# v2.net
KiCad netlist of a schematic drawn in EAGLE
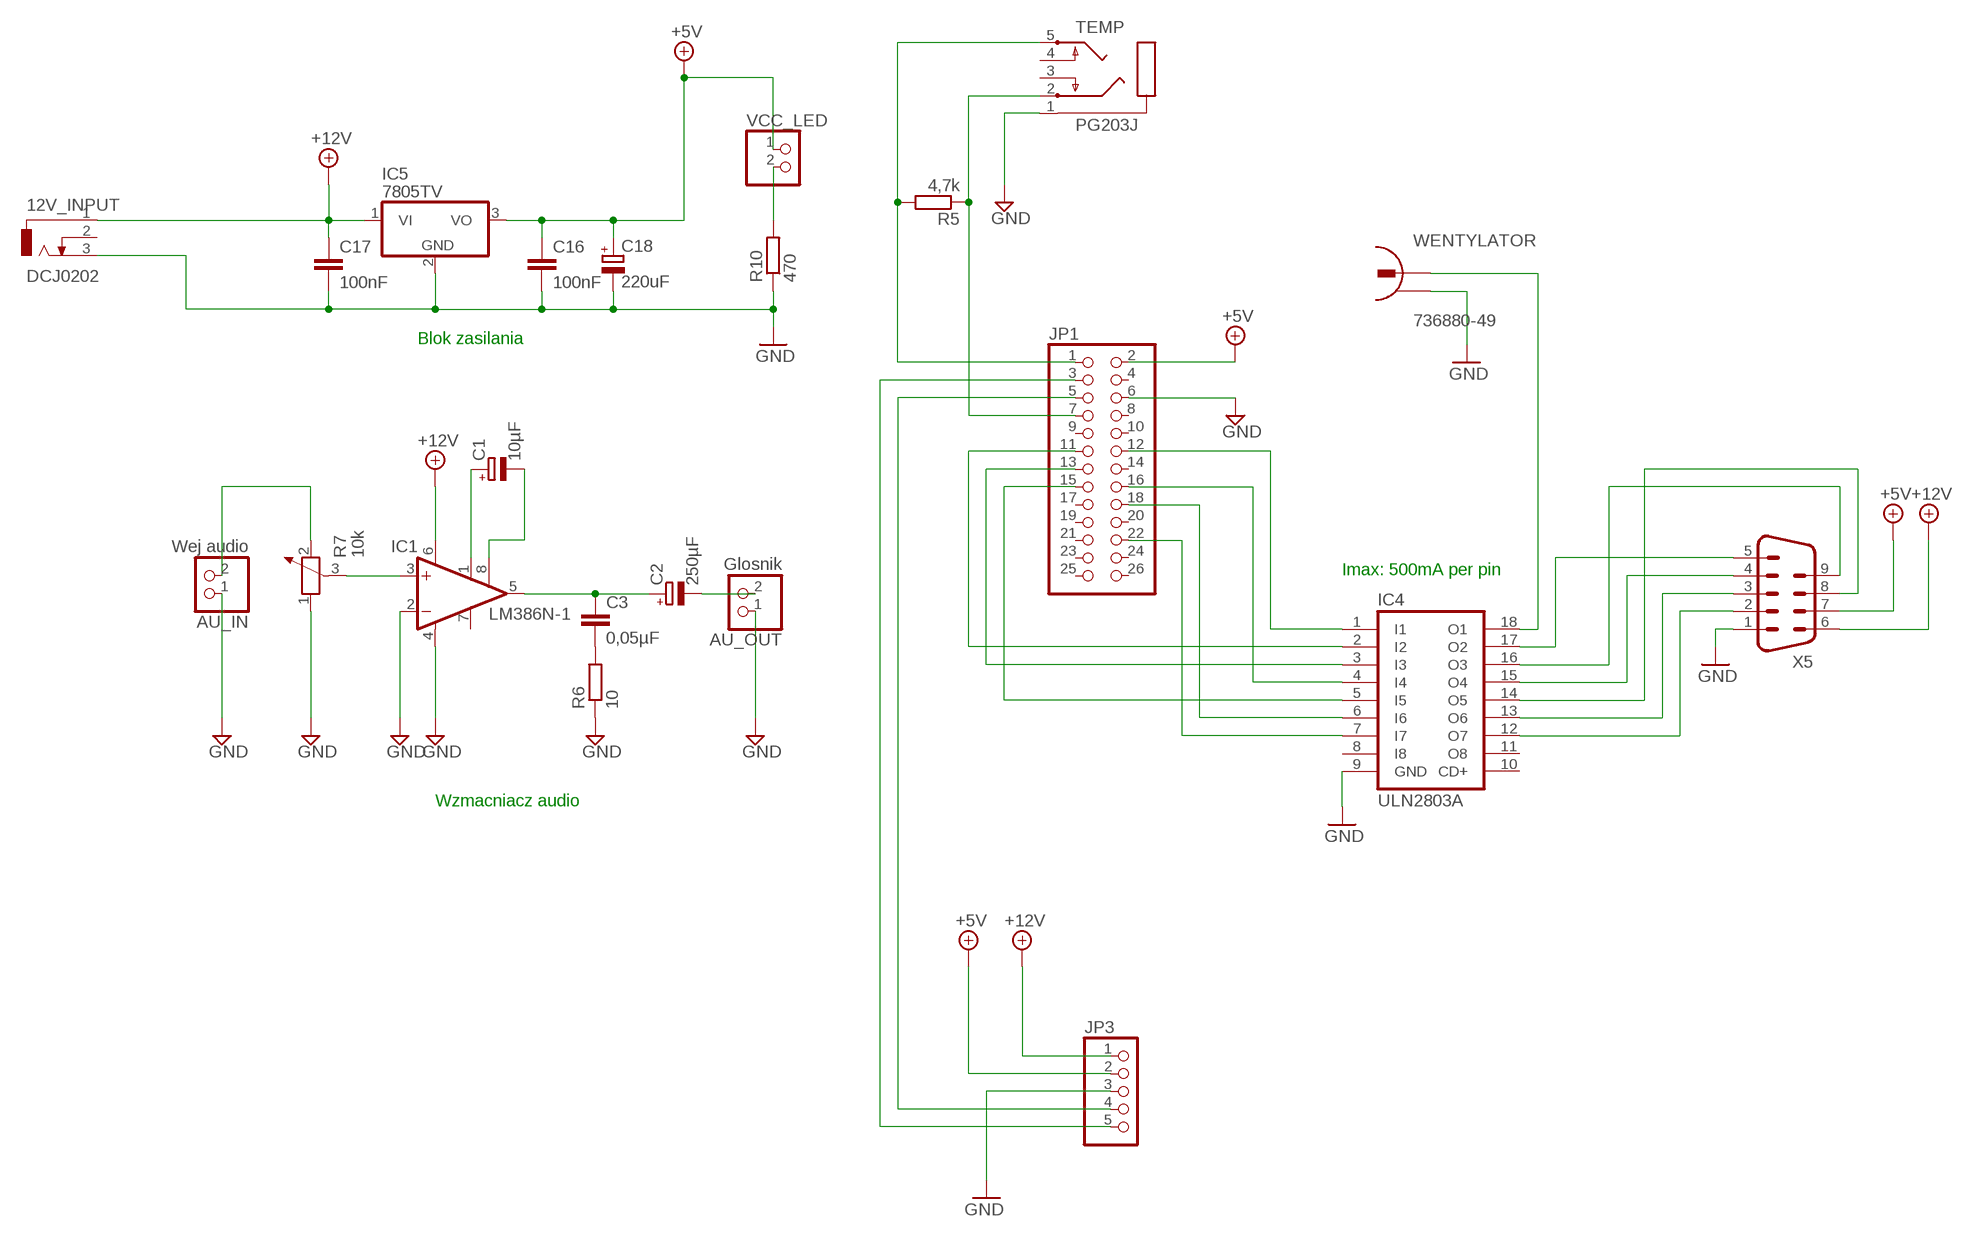
[diagram p0: schematic, sheet 1]

(export (version "E")
  (design (tool "Eeschema 10.0.6"))
  (components
    (comp (ref "12V_INPUT")
      (value "DCJ0202")
      (footprint "eagle-import:DCJ0202")
      (libsource (lib "eagle-import") (part "DCJ0202"))
    )
    (comp (ref "AU_IN")
      (value "Wej audio")
      (footprint "eagle-import:1X02")
      (libsource (lib "eagle-import") (part "PINHD-1X2"))
    )
    (comp (ref "AU_OUT")
      (value "Glosnik")
      (footprint "eagle-import:1X02")
      (libsource (lib "eagle-import") (part "PINHD-1X2"))
    )
    (comp (ref "C1")
      (value "10µF")
      (footprint "eagle-import:E2,5-5")
      (libsource (lib "eagle-import") (part "rcl_CPOL-EUE2.5-5"))
    )
    (comp (ref "C2")
      (value "250µF")
      (footprint "eagle-import:E2,5-6")
      (libsource (lib "eagle-import") (part "rcl_CPOL-EUE2.5-6"))
    )
    (comp (ref "C3")
      (value "0,05µF")
      (footprint "eagle-import:C025-024X044")
      (libsource (lib "eagle-import") (part "rcl_C-EU025-024X044"))
    )
    (comp (ref "C16")
      (value "100nF")
      (footprint "eagle-import:C050-024X044")
      (libsource (lib "eagle-import") (part "C-EU050-024X044"))
    )
    (comp (ref "C17")
      (value "100nF")
      (footprint "eagle-import:C050-024X044")
      (libsource (lib "eagle-import") (part "C-EU050-024X044"))
    )
    (comp (ref "C18")
      (value "220uF")
      (footprint "eagle-import:E2,5-5")
      (libsource (lib "eagle-import") (part "CPOL-EUE2.5-5"))
    )
    (comp (ref "IC1")
      (value "LM386N-1")
      (footprint "eagle-import:DIL08")
      (libsource (lib "eagle-import") (part "LM386?-N1"))
    )
    (comp (ref "IC4")
      (value "ULN2803A")
      (footprint "eagle-import:DIL18")
      (libsource (lib "eagle-import") (part "ULN2803A"))
    )
    (comp (ref "IC5")
      (value "7805TV")
      (footprint "eagle-import:TO220V")
      (libsource (lib "eagle-import") (part "78TV05"))
    )
    (comp (ref "JP1")
      (value "PINHD-2X13")
      (footprint "eagle-import:2X13")
      (libsource (lib "eagle-import") (part "PINHD-2X13"))
    )
    (comp (ref "JP3")
      (value "PINHD-1X5/90")
      (footprint "eagle-import:1X05_90")
      (libsource (lib "eagle-import") (part "PINHD-1X5/90"))
    )
    (comp (ref "R5")
      (value "4,7k")
      (footprint "eagle-import:R1206")
      (libsource (lib "eagle-import") (part "R-EU_R1206"))
    )
    (comp (ref "R6")
      (value "10")
      (footprint "eagle-import:R1206")
      (libsource (lib "eagle-import") (part "R-EU_R1206"))
    )
    (comp (ref "R7")
      (value "10k")
      (footprint "eagle-import:PT-10")
      (libsource (lib "eagle-import") (part "POTENTIOMETER_PT-10"))
    )
    (comp (ref "R10")
      (value "470")
      (footprint "eagle-import:R1206")
      (libsource (lib "eagle-import") (part "R-EU_R1206"))
    )
    (comp (ref "TEMP")
      (value "PG203J")
      (footprint "eagle-import:PG203J")
      (libsource (lib "eagle-import") (part "PG203J"))
    )
    (comp (ref "VCC_LED")
      (value "PINHD-1X2")
      (footprint "eagle-import:1X02")
      (libsource (lib "eagle-import") (part "PINHD-1X2"))
    )
    (comp (ref "WENTYLATOR")
      (value "736880-49")
      (footprint "eagle-import:736880-49")
      (libsource (lib "eagle-import") (part "736880-49"))
    )
    (comp (ref "X5")
      (value "M09H")
      (footprint "eagle-import:M09H")
      (libsource (lib "eagle-import") (part "M09H"))
    )
  )
  (nets
    (net (code "1") (name "+5V") (class "Default")
      (node (ref "C16") (pin "1") (pinfunction "1_1") (pintype "passive"))
      (node (ref "C18") (pin "+") (pinfunction "+_+") (pintype "passive"))
      (node (ref "IC5") (pin "3") (pinfunction "VO_3") (pintype "passive"))
      (node (ref "JP1") (pin "2") (pinfunction "2_2") (pintype "passive"))
      (node (ref "JP3") (pin "2") (pinfunction "2_2") (pintype "passive"))
      (node (ref "VCC_LED") (pin "1") (pinfunction "1_1") (pintype "passive"))
      (node (ref "X5") (pin "7") (pinfunction "7_7") (pintype "passive"))
    )
    (net (code "2") (name "+12V") (class "Default")
      (node (ref "12V_INPUT") (pin "1") (pinfunction "1_1") (pintype "passive"))
      (node (ref "C17") (pin "1") (pinfunction "1_1") (pintype "passive"))
      (node (ref "IC1") (pin "6") (pinfunction "VS_6") (pintype "power_in"))
      (node (ref "IC5") (pin "1") (pinfunction "VI_1") (pintype "input"))
      (node (ref "JP3") (pin "1") (pinfunction "1_1") (pintype "passive"))
      (node (ref "X5") (pin "6") (pinfunction "6_6") (pintype "passive"))
    )
    (net (code "3") (name "GND") (class "Default")
      (node (ref "12V_INPUT") (pin "3") (pinfunction "3_3") (pintype "passive"))
      (node (ref "AU_IN") (pin "1") (pinfunction "1_1") (pintype "passive"))
      (node (ref "AU_OUT") (pin "1") (pinfunction "1_1") (pintype "passive"))
      (node (ref "C16") (pin "2") (pinfunction "2_2") (pintype "passive"))
      (node (ref "C17") (pin "2") (pinfunction "2_2") (pintype "passive"))
      (node (ref "C18") (pin "-") (pinfunction "-_-") (pintype "passive"))
      (node (ref "IC1") (pin "2") (pinfunction "-IN_2") (pintype "input"))
      (node (ref "IC1") (pin "4") (pinfunction "GND_4") (pintype "power_in"))
      (node (ref "IC4") (pin "9") (pinfunction "GND_9") (pintype "power_in"))
      (node (ref "IC5") (pin "2") (pinfunction "GND_2") (pintype "passive"))
      (node (ref "JP1") (pin "6") (pinfunction "6_6") (pintype "passive"))
      (node (ref "JP3") (pin "3") (pinfunction "3_3") (pintype "passive"))
      (node (ref "R10") (pin "1") (pinfunction "1_1") (pintype "passive"))
      (node (ref "R6") (pin "1") (pinfunction "1_1") (pintype "passive"))
      (node (ref "R7") (pin "1") (pinfunction "1_1") (pintype "passive"))
      (node (ref "TEMP") (pin "1") (pinfunction "1_1") (pintype "passive"))
      (node (ref "WENTYLATOR") (pin "2") (pinfunction "2_2") (pintype "passive"))
      (node (ref "X5") (pin "1") (pinfunction "1_1") (pintype "passive"))
    )
    (net (code "4") (name "Net-(AU_IN-Pad2)") (class "Default")
      (node (ref "AU_IN") (pin "2") (pinfunction "2_2") (pintype "passive"))
      (node (ref "R7") (pin "2") (pinfunction "2_2") (pintype "passive"))
    )
    (net (code "5") (name "Net-(AU_OUT-Pad2)") (class "Default")
      (node (ref "AU_OUT") (pin "2") (pinfunction "2_2") (pintype "passive"))
      (node (ref "C2") (pin "-") (pinfunction "-_-") (pintype "passive"))
    )
    (net (code "6") (name "Net-(C1-Pad+)") (class "Default")
      (node (ref "C1") (pin "+") (pinfunction "+_+") (pintype "passive"))
      (node (ref "IC1") (pin "1") (pinfunction "GAIN_1") (pintype "passive"))
    )
    (net (code "7") (name "Net-(C1-Pad-)") (class "Default")
      (node (ref "C1") (pin "-") (pinfunction "-_-") (pintype "passive"))
      (node (ref "IC1") (pin "8") (pinfunction "GAIN_8") (pintype "passive"))
    )
    (net (code "8") (name "Net-(C3-Pad2)") (class "Default")
      (node (ref "C3") (pin "2") (pinfunction "2_2") (pintype "passive"))
      (node (ref "R6") (pin "2") (pinfunction "2_2") (pintype "passive"))
    )
    (net (code "9") (name "Net-(IC1-+IN)") (class "Default")
      (node (ref "IC1") (pin "3") (pinfunction "+IN_3") (pintype "input"))
      (node (ref "R7") (pin "3") (pinfunction "3_3") (pintype "passive"))
    )
    (net (code "10") (name "Net-(IC1-OUT)") (class "Default")
      (node (ref "C2") (pin "+") (pinfunction "+_+") (pintype "passive"))
      (node (ref "C3") (pin "1") (pinfunction "1_1") (pintype "passive"))
      (node (ref "IC1") (pin "5") (pinfunction "OUT_5") (pintype "output"))
    )
    (net (code "11") (name "Net-(IC4-I1)") (class "Default")
      (node (ref "IC4") (pin "1") (pinfunction "I1_1") (pintype "input"))
      (node (ref "JP1") (pin "12") (pinfunction "12_12") (pintype "passive"))
    )
    (net (code "12") (name "Net-(IC4-I2)") (class "Default")
      (node (ref "IC4") (pin "2") (pinfunction "I2_2") (pintype "input"))
      (node (ref "JP1") (pin "11") (pinfunction "11_11") (pintype "passive"))
    )
    (net (code "13") (name "Net-(IC4-I3)") (class "Default")
      (node (ref "IC4") (pin "3") (pinfunction "I3_3") (pintype "input"))
      (node (ref "JP1") (pin "13") (pinfunction "13_13") (pintype "passive"))
    )
    (net (code "14") (name "Net-(IC4-I4)") (class "Default")
      (node (ref "IC4") (pin "4") (pinfunction "I4_4") (pintype "input"))
      (node (ref "JP1") (pin "16") (pinfunction "16_16") (pintype "passive"))
    )
    (net (code "15") (name "Net-(IC4-I5)") (class "Default")
      (node (ref "IC4") (pin "5") (pinfunction "I5_5") (pintype "input"))
      (node (ref "JP1") (pin "15") (pinfunction "15_15") (pintype "passive"))
    )
    (net (code "16") (name "Net-(IC4-I6)") (class "Default")
      (node (ref "IC4") (pin "6") (pinfunction "I6_6") (pintype "input"))
      (node (ref "JP1") (pin "18") (pinfunction "18_18") (pintype "passive"))
    )
    (net (code "17") (name "Net-(IC4-I7)") (class "Default")
      (node (ref "IC4") (pin "7") (pinfunction "I7_7") (pintype "input"))
      (node (ref "JP1") (pin "22") (pinfunction "22_22") (pintype "passive"))
    )
    (net (code "18") (name "Net-(IC4-O1)") (class "Default")
      (node (ref "IC4") (pin "18") (pinfunction "O1_18") (pintype "open_collector"))
      (node (ref "WENTYLATOR") (pin "1") (pinfunction "1_1") (pintype "passive"))
    )
    (net (code "19") (name "Net-(IC4-O2)") (class "Default")
      (node (ref "IC4") (pin "17") (pinfunction "O2_17") (pintype "open_collector"))
      (node (ref "X5") (pin "5") (pinfunction "5_5") (pintype "passive"))
    )
    (net (code "20") (name "Net-(IC4-O3)") (class "Default")
      (node (ref "IC4") (pin "16") (pinfunction "O3_16") (pintype "open_collector"))
      (node (ref "X5") (pin "9") (pinfunction "9_9") (pintype "passive"))
    )
    (net (code "21") (name "Net-(IC4-O4)") (class "Default")
      (node (ref "IC4") (pin "15") (pinfunction "O4_15") (pintype "open_collector"))
      (node (ref "X5") (pin "4") (pinfunction "4_4") (pintype "passive"))
    )
    (net (code "22") (name "Net-(IC4-O5)") (class "Default")
      (node (ref "IC4") (pin "14") (pinfunction "O5_14") (pintype "open_collector"))
      (node (ref "X5") (pin "8") (pinfunction "8_8") (pintype "passive"))
    )
    (net (code "23") (name "Net-(IC4-O6)") (class "Default")
      (node (ref "IC4") (pin "13") (pinfunction "O6_13") (pintype "open_collector"))
      (node (ref "X5") (pin "3") (pinfunction "3_3") (pintype "passive"))
    )
    (net (code "24") (name "Net-(IC4-O7)") (class "Default")
      (node (ref "IC4") (pin "12") (pinfunction "O7_12") (pintype "open_collector"))
      (node (ref "X5") (pin "2") (pinfunction "2_2") (pintype "passive"))
    )
    (net (code "25") (name "Net-(JP1-Pad1)") (class "Default")
      (node (ref "JP1") (pin "1") (pinfunction "1_1") (pintype "passive"))
      (node (ref "R5") (pin "2") (pinfunction "2_2") (pintype "passive"))
      (node (ref "TEMP") (pin "5") (pinfunction "5_5") (pintype "passive"))
    )
    (net (code "26") (name "Net-(JP1-Pad3)") (class "Default")
      (node (ref "JP1") (pin "3") (pinfunction "3_3") (pintype "passive"))
      (node (ref "JP3") (pin "5") (pinfunction "5_5") (pintype "passive"))
    )
    (net (code "27") (name "Net-(JP1-Pad5)") (class "Default")
      (node (ref "JP1") (pin "5") (pinfunction "5_5") (pintype "passive"))
      (node (ref "JP3") (pin "4") (pinfunction "4_4") (pintype "passive"))
    )
    (net (code "28") (name "Net-(JP1-Pad7)") (class "Default")
      (node (ref "JP1") (pin "7") (pinfunction "7_7") (pintype "passive"))
      (node (ref "R5") (pin "1") (pinfunction "1_1") (pintype "passive"))
      (node (ref "TEMP") (pin "2") (pinfunction "2_2") (pintype "passive"))
    )
    (net (code "29") (name "Net-(R10-Pad2)") (class "Default")
      (node (ref "R10") (pin "2") (pinfunction "2_2") (pintype "passive"))
      (node (ref "VCC_LED") (pin "2") (pinfunction "2_2") (pintype "passive"))
    )
    (net (code "30") (name "unconnected-(12V_INPUT-Pad2)") (class "Default")
      (node (ref "12V_INPUT") (pin "2") (pinfunction "2_2") (pintype "passive"))
    )
    (net (code "31") (name "unconnected-(IC1-BYPASS-Pad7)") (class "Default")
      (node (ref "IC1") (pin "7") (pinfunction "BYPASS_7") (pintype "passive"))
    )
    (net (code "32") (name "unconnected-(IC4-CD+-Pad10)") (class "Default")
      (node (ref "IC4") (pin "10") (pinfunction "CD+_10") (pintype "passive"))
    )
    (net (code "33") (name "unconnected-(IC4-I8-Pad8)") (class "Default")
      (node (ref "IC4") (pin "8") (pinfunction "I8_8") (pintype "input"))
    )
    (net (code "34") (name "unconnected-(IC4-O8-Pad11)") (class "Default")
      (node (ref "IC4") (pin "11") (pinfunction "O8_11") (pintype "open_collector"))
    )
    (net (code "35") (name "unconnected-(JP1-Pad4)") (class "Default")
      (node (ref "JP1") (pin "4") (pinfunction "4_4") (pintype "passive"))
    )
    (net (code "36") (name "unconnected-(JP1-Pad8)") (class "Default")
      (node (ref "JP1") (pin "8") (pinfunction "8_8") (pintype "passive"))
    )
    (net (code "37") (name "unconnected-(JP1-Pad9)") (class "Default")
      (node (ref "JP1") (pin "9") (pinfunction "9_9") (pintype "passive"))
    )
    (net (code "38") (name "unconnected-(JP1-Pad10)") (class "Default")
      (node (ref "JP1") (pin "10") (pinfunction "10_10") (pintype "passive"))
    )
    (net (code "39") (name "unconnected-(JP1-Pad14)") (class "Default")
      (node (ref "JP1") (pin "14") (pinfunction "14_14") (pintype "passive"))
    )
    (net (code "40") (name "unconnected-(JP1-Pad17)") (class "Default")
      (node (ref "JP1") (pin "17") (pinfunction "17_17") (pintype "passive"))
    )
    (net (code "41") (name "unconnected-(JP1-Pad19)") (class "Default")
      (node (ref "JP1") (pin "19") (pinfunction "19_19") (pintype "passive"))
    )
    (net (code "42") (name "unconnected-(JP1-Pad20)") (class "Default")
      (node (ref "JP1") (pin "20") (pinfunction "20_20") (pintype "passive"))
    )
    (net (code "43") (name "unconnected-(JP1-Pad21)") (class "Default")
      (node (ref "JP1") (pin "21") (pinfunction "21_21") (pintype "passive"))
    )
    (net (code "44") (name "unconnected-(JP1-Pad23)") (class "Default")
      (node (ref "JP1") (pin "23") (pinfunction "23_23") (pintype "passive"))
    )
    (net (code "45") (name "unconnected-(JP1-Pad24)") (class "Default")
      (node (ref "JP1") (pin "24") (pinfunction "24_24") (pintype "passive"))
    )
    (net (code "46") (name "unconnected-(JP1-Pad25)") (class "Default")
      (node (ref "JP1") (pin "25") (pinfunction "25_25") (pintype "passive"))
    )
    (net (code "47") (name "unconnected-(JP1-Pad26)") (class "Default")
      (node (ref "JP1") (pin "26") (pinfunction "26_26") (pintype "passive"))
    )
    (net (code "48") (name "unconnected-(TEMP-Pad3)") (class "Default")
      (node (ref "TEMP") (pin "3") (pinfunction "3_3") (pintype "passive"))
    )
    (net (code "49") (name "unconnected-(TEMP-Pad4)") (class "Default")
      (node (ref "TEMP") (pin "4") (pinfunction "4_4") (pintype "passive"))
    )
    (net (code "50") (name "unconnected-(WENTYLATOR-2-Pad2@2)") (class "Default")
      (node (ref "WENTYLATOR") (pin "2@2") (pinfunction "2_2@2") (pintype "passive"))
    )
  )
)
